# Lumen.net
KiCad netlist of a schematic drawn in EAGLE
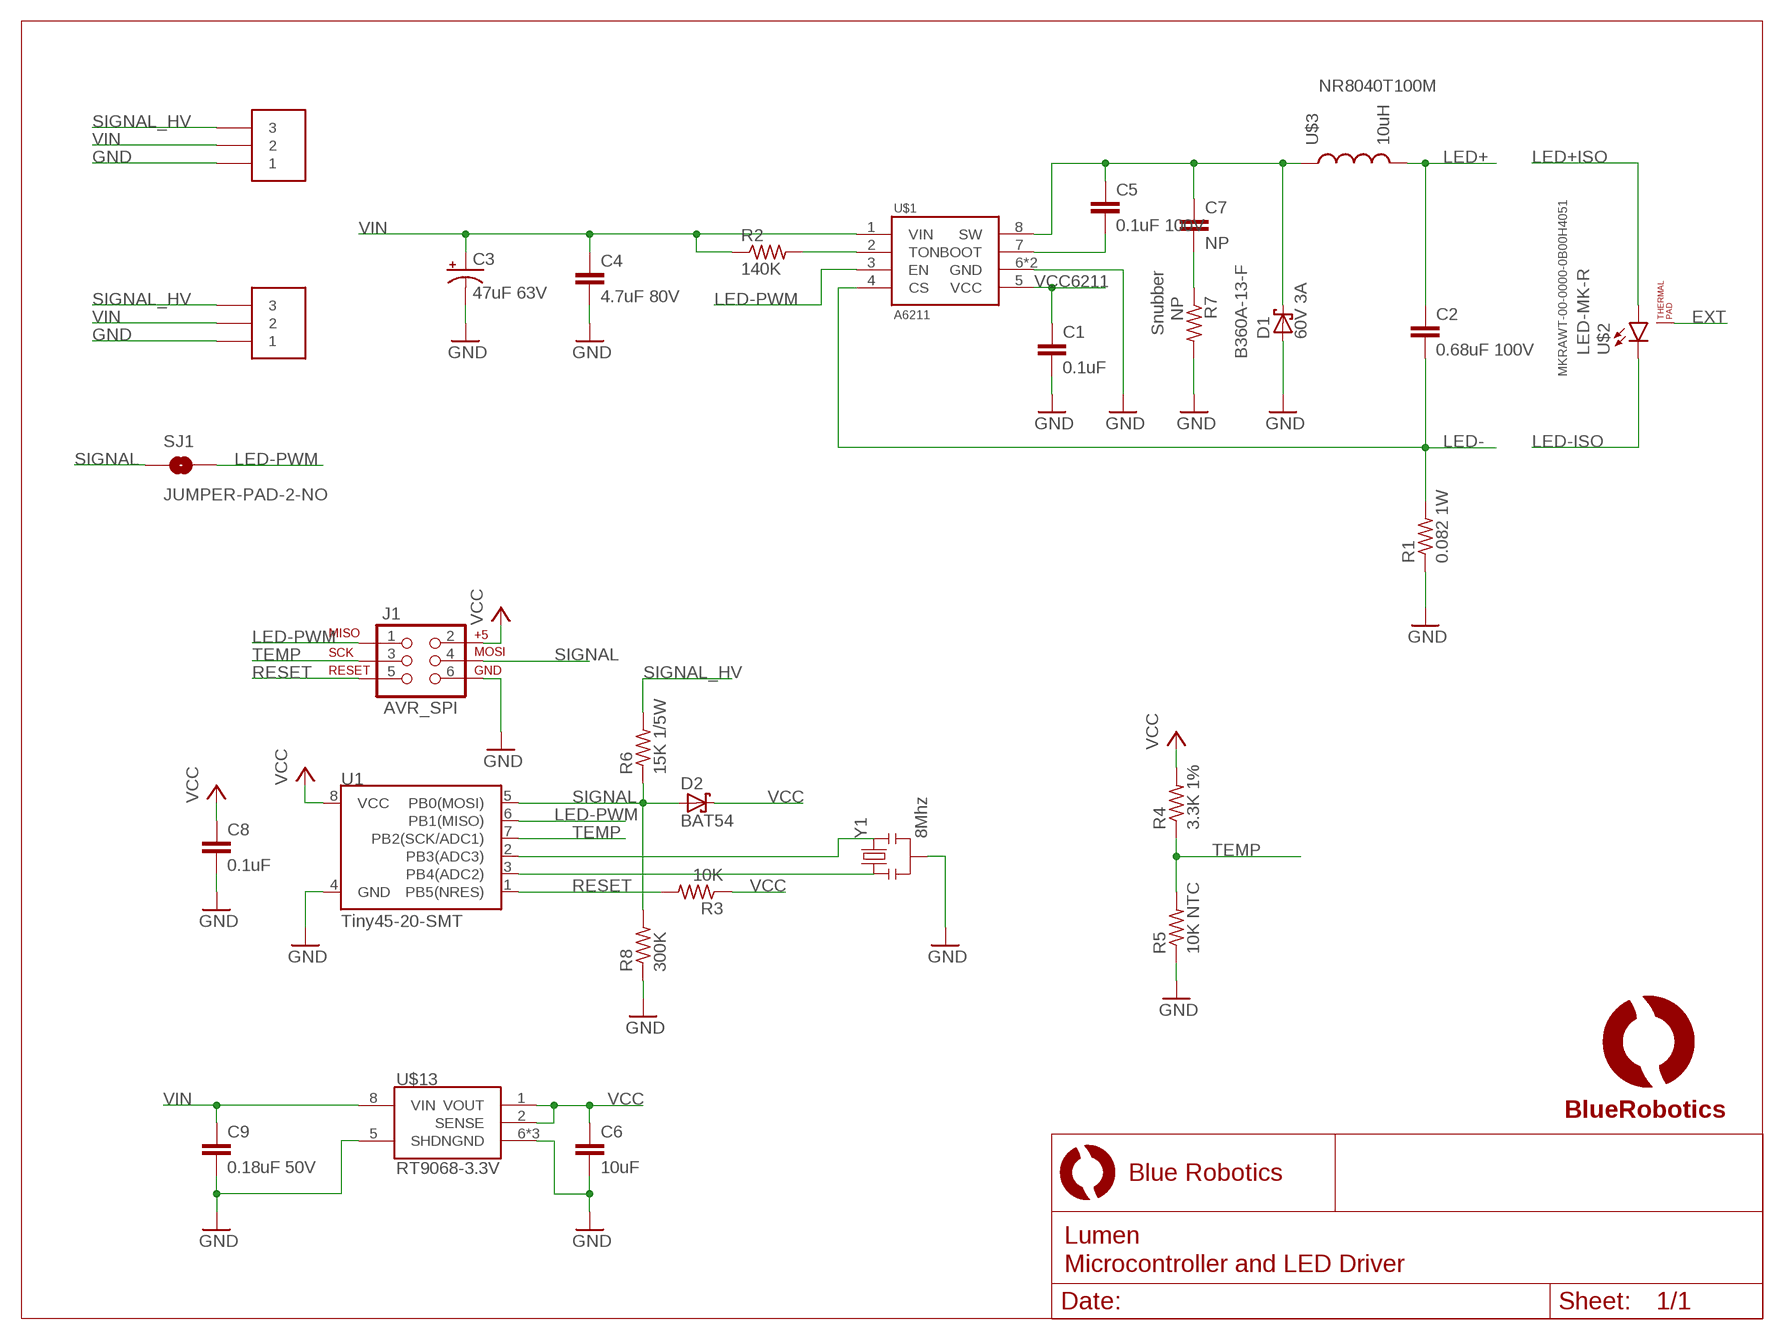
[diagram p0: schematic, sheet 1]

(export (version "E")
  (design (tool "Eeschema 10.0.6"))
  (components
    (comp (ref "C1")
      (value "0.1uF")
      (footprint "eagle-import:C0603")
      (libsource (lib "eagle-import") (part "C-EUC0603"))
    )
    (comp (ref "C2")
      (value "0.68uF 100V")
      (footprint "eagle-import:C0805")
      (libsource (lib "eagle-import") (part "C-EUC0805"))
    )
    (comp (ref "C3")
      (value "47uF 63V")
      (footprint "eagle-import:CPOL-RADIAL-100UF-25V")
      (libsource (lib "eagle-import") (part "CAP_POLPTH1"))
    )
    (comp (ref "C4")
      (value "4.7uF 80V")
      (footprint "eagle-import:C1210")
      (libsource (lib "eagle-import") (part "C-EUC1210"))
    )
    (comp (ref "C5")
      (value "0.1uF 100V")
      (footprint "eagle-import:C0805")
      (libsource (lib "eagle-import") (part "C-EUC0805"))
    )
    (comp (ref "C6")
      (value "10uF")
      (footprint "eagle-import:C0603")
      (libsource (lib "eagle-import") (part "C-EUC0603"))
    )
    (comp (ref "C7")
      (value "NP")
      (footprint "eagle-import:C0603")
      (libsource (lib "eagle-import") (part "C-EUC0603"))
    )
    (comp (ref "C8")
      (value "0.1uF")
      (footprint "eagle-import:C0603")
      (libsource (lib "eagle-import") (part "C-EUC0603"))
    )
    (comp (ref "C9")
      (value "0.18uF 50V")
      (footprint "eagle-import:C0805")
      (libsource (lib "eagle-import") (part "C-EUC0805"))
    )
    (comp (ref "D1")
      (value "60V 3A")
      (footprint "eagle-import:SMA")
      (libsource (lib "eagle-import") (part "DIODE-SCHOTTKYSMA"))
    )
    (comp (ref "D2")
      (value "BAT54")
      (footprint "eagle-import:SOD523")
      (libsource (lib "eagle-import") (part "DIODE-SCHOTTKYSOD523"))
    )
    (comp (ref "J1")
      (value "AVR_SPI")
      (footprint "eagle-import:2X3")
      (libsource (lib "eagle-import") (part "AVR_SPI_PRG_6PTH"))
    )
    (comp (ref "R1")
      (value "0.082 1W")
      (footprint "eagle-import:R2512")
      (libsource (lib "eagle-import") (part "R-US_R2512"))
    )
    (comp (ref "R2")
      (value "140K")
      (footprint "eagle-import:R0603")
      (libsource (lib "eagle-import") (part "R-US_R0603"))
    )
    (comp (ref "R3")
      (value "10K")
      (footprint "eagle-import:R0603")
      (libsource (lib "eagle-import") (part "R-US_R0603"))
    )
    (comp (ref "R4")
      (value "3.3K 1%")
      (footprint "eagle-import:R0603")
      (libsource (lib "eagle-import") (part "R-US_R0603"))
    )
    (comp (ref "R5")
      (value "10K NTC")
      (footprint "eagle-import:R0603")
      (libsource (lib "eagle-import") (part "R-US_R0603"))
    )
    (comp (ref "R6")
      (value "15K 1/5W")
      (footprint "eagle-import:R0402")
      (libsource (lib "eagle-import") (part "RESISTOR_0402"))
    )
    (comp (ref "R7")
      (value "NP")
      (footprint "eagle-import:R1206")
      (libsource (lib "eagle-import") (part "R-US_R1206"))
    )
    (comp (ref "R8")
      (value "300K")
      (footprint "eagle-import:R0402")
      (libsource (lib "eagle-import") (part "RESISTOR_0402"))
    )
    (comp (ref "SJ1")
      (value "JUMPER-PAD-2-NO")
      (footprint "eagle-import:PAD-JUMPER-2-NO_NO_SILK")
      (libsource (lib "eagle-import") (part "JUMPER-PAD-2-NO"))
    )
    (comp (ref "U$1")
      (value "A6211")
      (footprint "eagle-import:SOIC8N-LJ")
      (libsource (lib "eagle-import") (part "A6211"))
    )
    (comp (ref "U$2")
      (value "LED-MK-R")
      (footprint "eagle-import:MK-R")
      (libsource (lib "eagle-import") (part "LED-MK-R"))
    )
    (comp (ref "U$3")
      (value "10uH")
      (footprint "eagle-import:INDUCTOR-8040")
      (libsource (lib "eagle-import") (part "INDUCTOR8040"))
    )
    (comp (ref "U$10")
      (value "LOGOBR-LOGO-MS-COPPER")
      (footprint "eagle-import:BR-LOGO-MEDIUM-SMALL-COPPER")
      (libsource (lib "eagle-import") (part "LOGOBR-LOGO-MS-COPPER"))
    )
    (comp (ref "U$11")
      (value "009176003032006")
      (footprint "eagle-import:AVX-9176-3POS")
      (libsource (lib "eagle-import") (part "HEADER-3AVX-9176"))
    )
    (comp (ref "U$12")
      (value "009176003032006")
      (footprint "eagle-import:AVX-9176-3POS")
      (libsource (lib "eagle-import") (part "HEADER-3AVX-9176"))
    )
    (comp (ref "U$13")
      (value "RT9068-3.3V")
      (footprint "eagle-import:SOIC8N-LJ")
      (libsource (lib "eagle-import") (part "VREG-RT9068SOP-8"))
    )
    (comp (ref "U1")
      (value "Tiny45-20-SMT")
      (footprint "eagle-import:SO08-EIAJ")
      (libsource (lib "eagle-import") (part "ATTINY45TINY45-20-SMT"))
    )
    (comp (ref "Y1")
      (value "8Mhz")
      (footprint "eagle-import:RESONATOR-SMD")
      (libsource (lib "eagle-import") (part "RESONATORSMD"))
    )
  )
  (nets
    (net (code "1") (name "/EXT") (class "Default")
      (node (ref "U$2") (pin "EXP") (pinfunction "THERMAL_EXP") (pintype "bidirectional"))
    )
    (net (code "2") (name "/LED+") (class "Default")
      (node (ref "C2") (pin "1") (pinfunction "1_1") (pintype "passive"))
      (node (ref "U$3") (pin "P$2") (pinfunction "2_P$2") (pintype "passive"))
    )
    (net (code "3") (name "/LED+ISO") (class "Default")
      (node (ref "U$2") (pin "A") (pinfunction "A_A") (pintype "passive"))
    )
    (net (code "4") (name "/LED-") (class "Default")
      (node (ref "C2") (pin "2") (pinfunction "2_2") (pintype "passive"))
      (node (ref "R1") (pin "2") (pinfunction "2_2") (pintype "passive"))
      (node (ref "U$1") (pin "4") (pinfunction "CS_4") (pintype "bidirectional"))
    )
    (net (code "5") (name "/LED-ISO") (class "Default")
      (node (ref "U$2") (pin "C") (pinfunction "C_C") (pintype "passive"))
    )
    (net (code "6") (name "/LED-PWM") (class "Default")
      (node (ref "J1") (pin "1") (pinfunction "1_1") (pintype "passive"))
      (node (ref "SJ1") (pin "2") (pinfunction "2_2") (pintype "passive"))
      (node (ref "U$1") (pin "3") (pinfunction "EN_3") (pintype "bidirectional"))
      (node (ref "U1") (pin "6") (pinfunction "PB1(MISO)_6") (pintype "bidirectional"))
    )
    (net (code "7") (name "/RESET") (class "Default")
      (node (ref "J1") (pin "5") (pinfunction "5_5") (pintype "passive"))
      (node (ref "R3") (pin "2") (pinfunction "2_2") (pintype "passive"))
      (node (ref "U1") (pin "1") (pinfunction "PB5(NRES)_1") (pintype "bidirectional"))
    )
    (net (code "8") (name "/SIGNAL") (class "Default")
      (node (ref "D2") (pin "A") (pinfunction "A_A") (pintype "passive"))
      (node (ref "J1") (pin "4") (pinfunction "4_4") (pintype "passive"))
      (node (ref "R6") (pin "1") (pinfunction "1_1") (pintype "passive"))
      (node (ref "R8") (pin "2") (pinfunction "2_2") (pintype "passive"))
      (node (ref "SJ1") (pin "1") (pinfunction "1_1") (pintype "passive"))
      (node (ref "U1") (pin "5") (pinfunction "PB0(MOSI)_5") (pintype "bidirectional"))
    )
    (net (code "9") (name "/SIGNAL_HV") (class "Default")
      (node (ref "R6") (pin "2") (pinfunction "2_2") (pintype "passive"))
      (node (ref "U$11") (pin "3") (pinfunction "3_3") (pintype "bidirectional"))
      (node (ref "U$12") (pin "3") (pinfunction "3_3") (pintype "bidirectional"))
    )
    (net (code "10") (name "/TEMP") (class "Default")
      (node (ref "J1") (pin "3") (pinfunction "3_3") (pintype "passive"))
      (node (ref "R4") (pin "1") (pinfunction "1_1") (pintype "passive"))
      (node (ref "R5") (pin "2") (pinfunction "2_2") (pintype "passive"))
      (node (ref "U1") (pin "7") (pinfunction "PB2(SCK/ADC1)_7") (pintype "bidirectional"))
    )
    (net (code "11") (name "/VCC6211") (class "Default")
      (node (ref "C1") (pin "1") (pinfunction "1_1") (pintype "passive"))
      (node (ref "U$1") (pin "5") (pinfunction "VCC_5") (pintype "bidirectional"))
    )
    (net (code "12") (name "/VIN") (class "Default")
      (node (ref "C3") (pin "1") (pinfunction "+_1") (pintype "passive"))
      (node (ref "C4") (pin "1") (pinfunction "1_1") (pintype "passive"))
      (node (ref "C9") (pin "1") (pinfunction "1_1") (pintype "passive"))
      (node (ref "R2") (pin "1") (pinfunction "1_1") (pintype "passive"))
      (node (ref "U$1") (pin "1") (pinfunction "VIN_1") (pintype "bidirectional"))
      (node (ref "U$11") (pin "2") (pinfunction "2_2") (pintype "bidirectional"))
      (node (ref "U$12") (pin "2") (pinfunction "2_2") (pintype "bidirectional"))
      (node (ref "U$13") (pin "8") (pinfunction "VIN_8") (pintype "bidirectional"))
    )
    (net (code "13") (name "GND") (class "Default")
      (node (ref "C1") (pin "2") (pinfunction "2_2") (pintype "passive"))
      (node (ref "C3") (pin "2") (pinfunction "-_2") (pintype "passive"))
      (node (ref "C4") (pin "2") (pinfunction "2_2") (pintype "passive"))
      (node (ref "C6") (pin "2") (pinfunction "2_2") (pintype "passive"))
      (node (ref "C8") (pin "2") (pinfunction "2_2") (pintype "passive"))
      (node (ref "C9") (pin "2") (pinfunction "2_2") (pintype "passive"))
      (node (ref "D1") (pin "A") (pinfunction "A_A") (pintype "passive"))
      (node (ref "J1") (pin "6") (pinfunction "6_6") (pintype "passive"))
      (node (ref "R1") (pin "1") (pinfunction "1_1") (pintype "passive"))
      (node (ref "R5") (pin "1") (pinfunction "1_1") (pintype "passive"))
      (node (ref "R7") (pin "2") (pinfunction "2_2") (pintype "passive"))
      (node (ref "R8") (pin "1") (pinfunction "1_1") (pintype "passive"))
      (node (ref "U$1") (pin "6") (pinfunction "GND_6") (pintype "bidirectional"))
      (node (ref "U$1") (pin "PAD") (pinfunction "GND_PAD") (pintype "bidirectional"))
      (node (ref "U$11") (pin "1") (pinfunction "1_1") (pintype "bidirectional"))
      (node (ref "U$12") (pin "1") (pinfunction "1_1") (pintype "bidirectional"))
      (node (ref "U$13") (pin "5") (pinfunction "SHDN_5") (pintype "bidirectional"))
      (node (ref "U$13") (pin "6") (pinfunction "GND_6") (pintype "bidirectional"))
      (node (ref "U$13") (pin "7") (pinfunction "GND_7") (pintype "bidirectional"))
      (node (ref "U$13") (pin "PAD") (pinfunction "GND_PAD") (pintype "bidirectional"))
      (node (ref "U1") (pin "4") (pinfunction "GND_4") (pintype "bidirectional"))
      (node (ref "Y1") (pin "2") (pinfunction "2_2") (pintype "passive"))
    )
    (net (code "14") (name "Net-(C7-Pad2)") (class "Default")
      (node (ref "C7") (pin "2") (pinfunction "2_2") (pintype "passive"))
      (node (ref "R7") (pin "1") (pinfunction "1_1") (pintype "passive"))
    )
    (net (code "15") (name "Net-(U$1-BOOT)") (class "Default")
      (node (ref "C5") (pin "2") (pinfunction "2_2") (pintype "passive"))
      (node (ref "U$1") (pin "7") (pinfunction "BOOT_7") (pintype "bidirectional"))
    )
    (net (code "16") (name "Net-(U$1-SW)") (class "Default")
      (node (ref "C5") (pin "1") (pinfunction "1_1") (pintype "passive"))
      (node (ref "C7") (pin "1") (pinfunction "1_1") (pintype "passive"))
      (node (ref "D1") (pin "C") (pinfunction "C_C") (pintype "passive"))
      (node (ref "U$1") (pin "8") (pinfunction "SW_8") (pintype "bidirectional"))
      (node (ref "U$3") (pin "P$1") (pinfunction "1_P$1") (pintype "passive"))
    )
    (net (code "17") (name "Net-(U$1-TON)") (class "Default")
      (node (ref "R2") (pin "2") (pinfunction "2_2") (pintype "passive"))
      (node (ref "U$1") (pin "2") (pinfunction "TON_2") (pintype "bidirectional"))
    )
    (net (code "18") (name "Net-(U1-PB3(ADC3))") (class "Default")
      (node (ref "U1") (pin "2") (pinfunction "PB3(ADC3)_2") (pintype "bidirectional"))
      (node (ref "Y1") (pin "3") (pinfunction "3_3") (pintype "passive"))
    )
    (net (code "19") (name "Net-(U1-PB4(ADC2))") (class "Default")
      (node (ref "U1") (pin "3") (pinfunction "PB4(ADC2)_3") (pintype "bidirectional"))
      (node (ref "Y1") (pin "1") (pinfunction "1_1") (pintype "passive"))
    )
    (net (code "20") (name "VCC") (class "Default")
      (node (ref "C6") (pin "1") (pinfunction "1_1") (pintype "passive"))
      (node (ref "C8") (pin "1") (pinfunction "1_1") (pintype "passive"))
      (node (ref "D2") (pin "C") (pinfunction "C_C") (pintype "passive"))
      (node (ref "J1") (pin "2") (pinfunction "2_2") (pintype "passive"))
      (node (ref "R3") (pin "1") (pinfunction "1_1") (pintype "passive"))
      (node (ref "R4") (pin "2") (pinfunction "2_2") (pintype "passive"))
      (node (ref "U$13") (pin "1") (pinfunction "VOUT_1") (pintype "bidirectional"))
      (node (ref "U$13") (pin "2") (pinfunction "SENSE_2") (pintype "bidirectional"))
      (node (ref "U1") (pin "8") (pinfunction "VCC_8") (pintype "bidirectional"))
    )
  )
)
